# ProDoc_HyperCardReader_2024-07-06.net
KiCad netlist of a schematic drawn in EasyEDA Pro
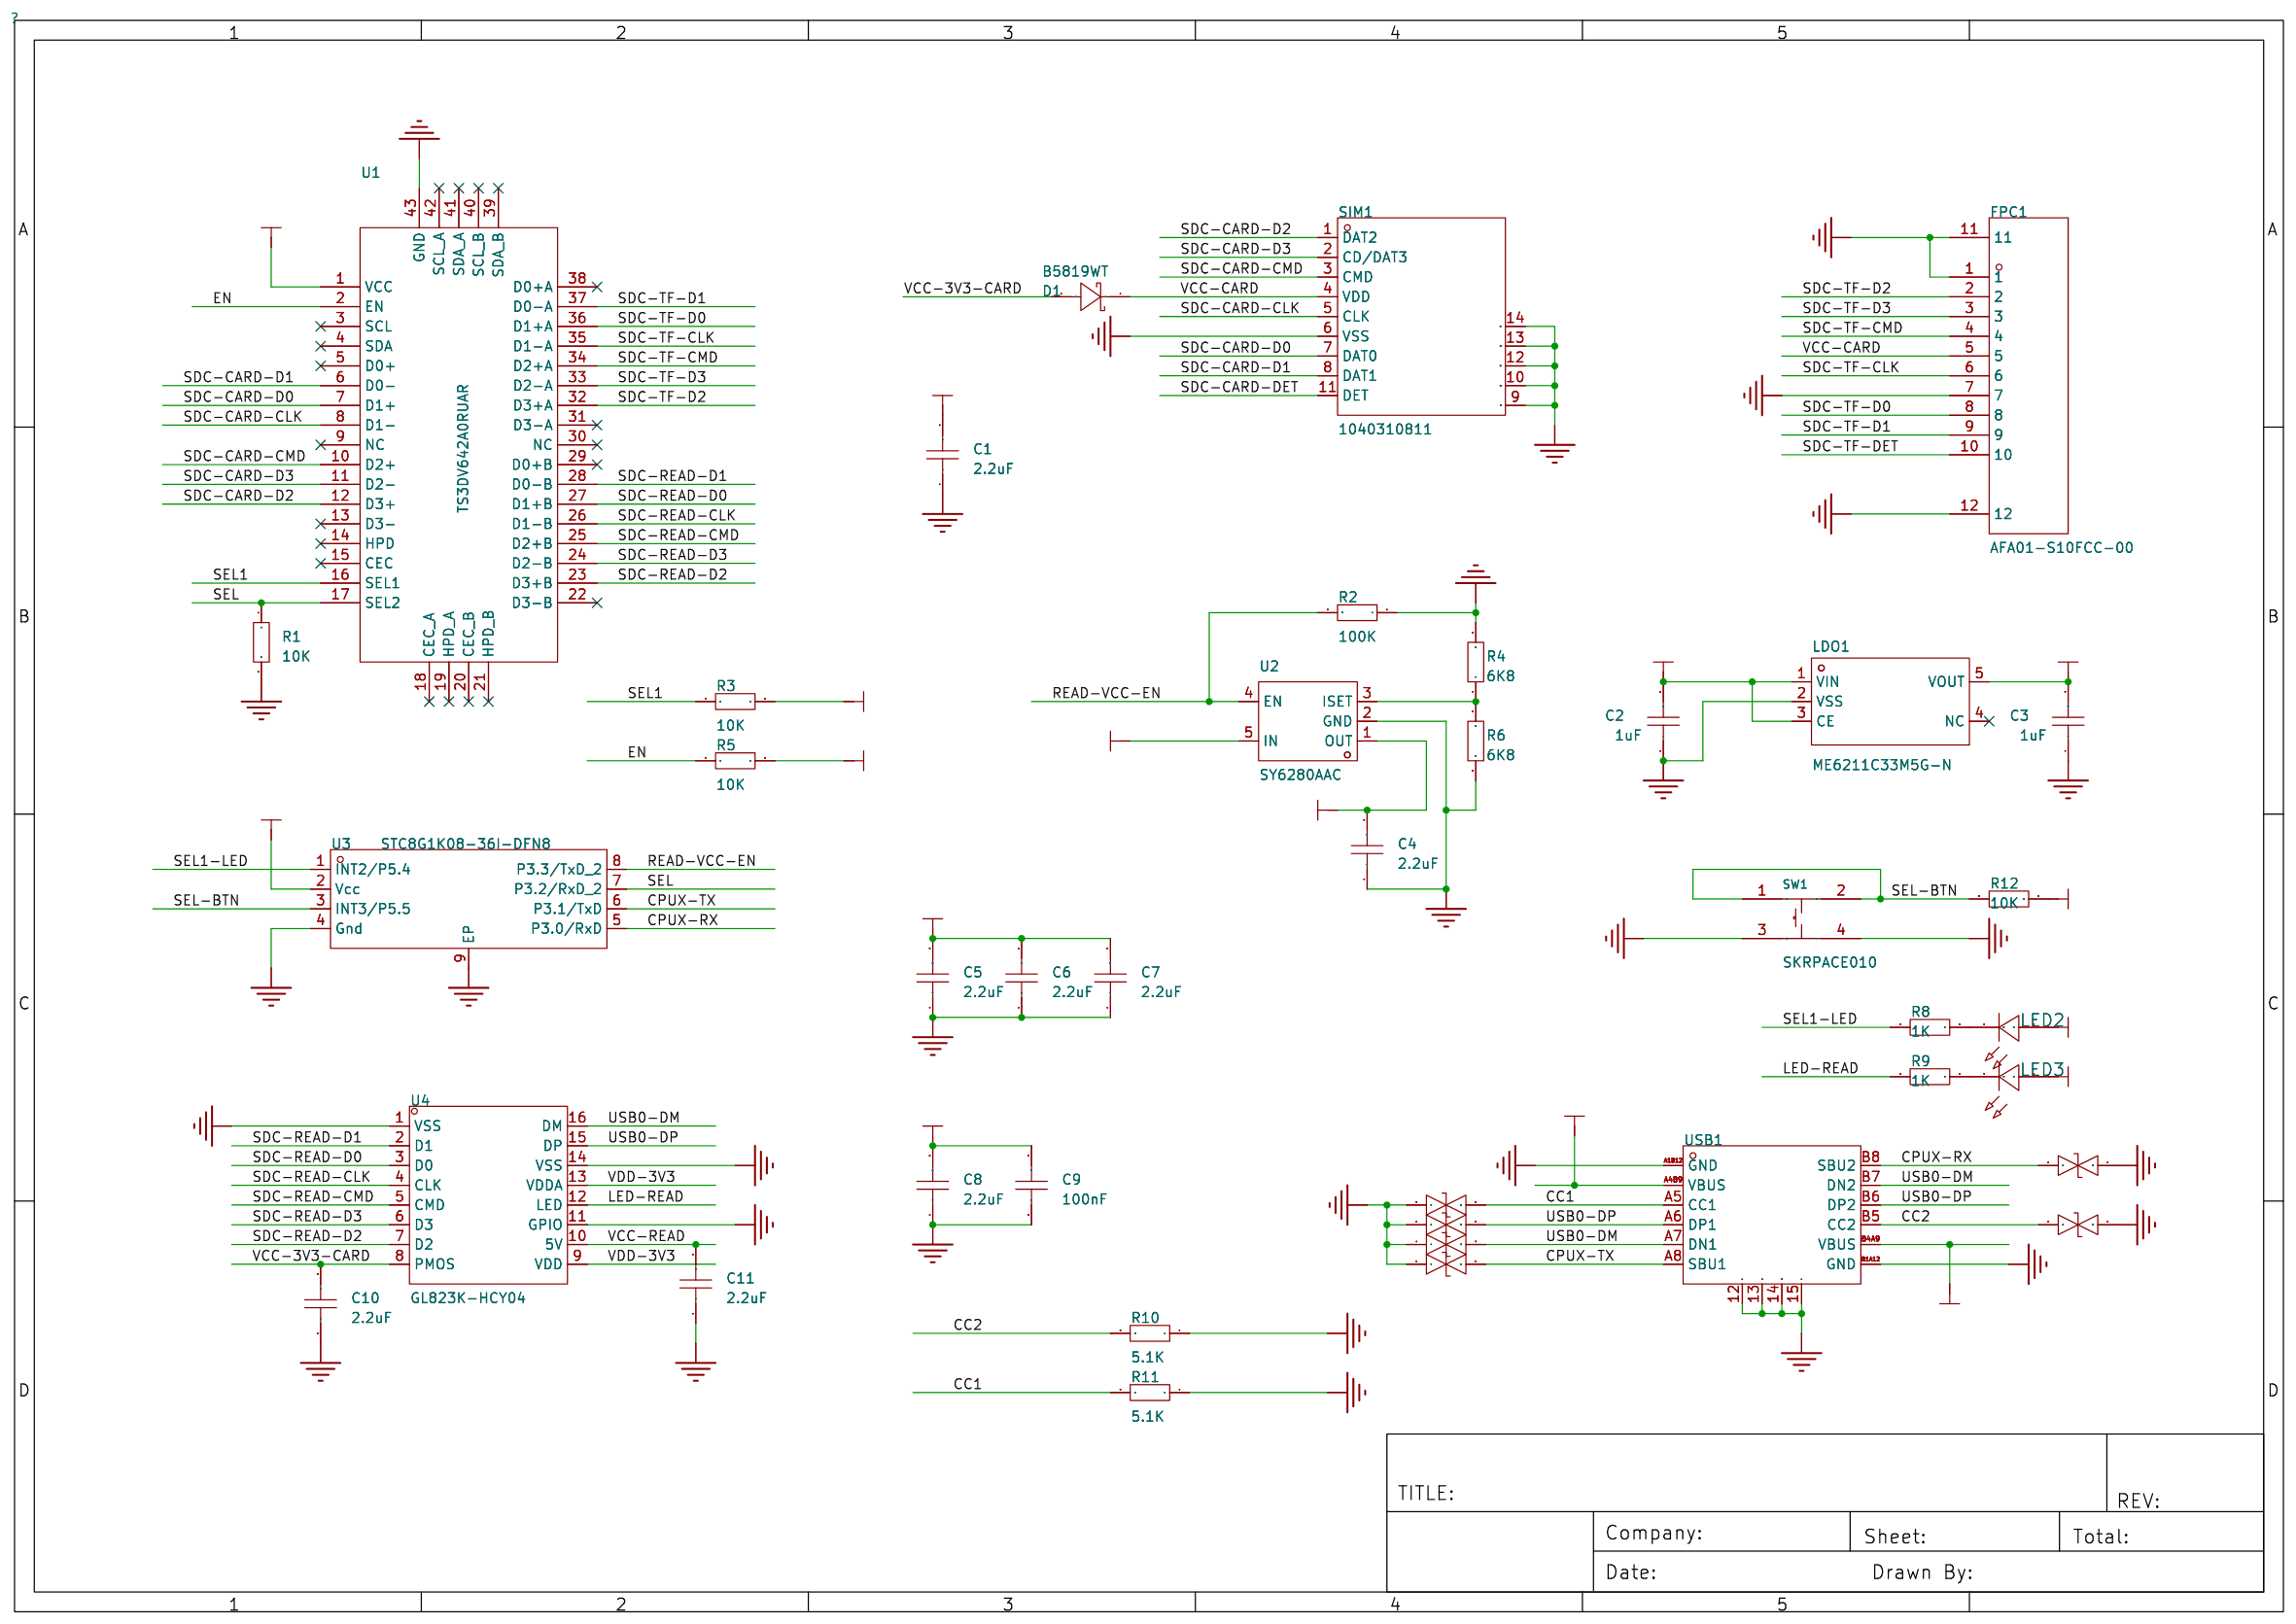
[diagram p0: schematic sheet]

(export (version "E")
  (design (tool "Eeschema 10.0.6"))
  (components
    (comp (ref "C1")
      (value "2.2uF")
      (footprint "easyedapro:C0402")
      (libsource (lib "easyedapro") (part "CapAcitance"))
    )
    (comp (ref "C2")
      (value "1uF")
      (footprint "easyedapro:C0402")
      (libsource (lib "easyedapro") (part "CapAcitance"))
    )
    (comp (ref "C3")
      (value "1uF")
      (footprint "easyedapro:C0402")
      (libsource (lib "easyedapro") (part "CapAcitance"))
    )
    (comp (ref "C4")
      (value "2.2uF")
      (footprint "easyedapro:C0402")
      (libsource (lib "easyedapro") (part "CapAcitance"))
    )
    (comp (ref "C5")
      (value "2.2uF")
      (footprint "easyedapro:C0402")
      (libsource (lib "easyedapro") (part "CapAcitance"))
    )
    (comp (ref "C6")
      (value "2.2uF")
      (footprint "easyedapro:C0402")
      (libsource (lib "easyedapro") (part "CapAcitance"))
    )
    (comp (ref "C7")
      (value "2.2uF")
      (footprint "easyedapro:C0402")
      (libsource (lib "easyedapro") (part "CapAcitance"))
    )
    (comp (ref "C8")
      (value "2.2uF")
      (footprint "easyedapro:C0402")
      (libsource (lib "easyedapro") (part "CapAcitance"))
    )
    (comp (ref "C9")
      (value "100nF")
      (footprint "easyedapro:C0402")
      (libsource (lib "easyedapro") (part "CapAcitance"))
    )
    (comp (ref "C10")
      (value "2.2uF")
      (footprint "easyedapro:C0402")
      (libsource (lib "easyedapro") (part "CapAcitance"))
    )
    (comp (ref "C11")
      (value "2.2uF")
      (footprint "easyedapro:C0402")
      (libsource (lib "easyedapro") (part "CapAcitance"))
    )
    (comp (ref "D1")
      (value "B5819WT")
      (footprint "easyedapro:SOD-523_L1.2-W0.8-LS1.6-RD")
      (description "二极管配置:-;正向压降(Vf):600mV@200mA;直流反向耐压(Vr):40V;平均整流电流(Io):1A;")
      (fields (field (name "Manufacturer") "BORN(伯恩半导体)"))
      (libsource (lib "easyedapro") (part "B5819WT_C2997265"))
    )
    (comp (ref "D2")
      (value "0402ESDA-05N")
      (footprint "easyedapro:D0402-BI")
      (description "极性:Bidirectional;反向关断电压（典型值）:5V;击穿电压（最小值）:-;箝位电压:50V;峰值脉冲电流（10/1000us）:-;")
      (fields (field (name "Manufacturer") "BORN伯恩半导体"))
      (libsource (lib "easyedapro") (part "0402ESDA-05N"))
    )
    (comp (ref "D3")
      (value "0402ESDA-05N")
      (footprint "easyedapro:D0402-BI")
      (description "极性:Bidirectional;反向关断电压（典型值）:5V;击穿电压（最小值）:-;箝位电压:50V;峰值脉冲电流（10/1000us）:-;")
      (fields (field (name "Manufacturer") "BORN伯恩半导体"))
      (libsource (lib "easyedapro") (part "0402ESDA-05N"))
    )
    (comp (ref "D4")
      (value "0402ESDA-05N")
      (footprint "easyedapro:D0402-BI")
      (description "极性:Bidirectional;反向关断电压（典型值）:5V;击穿电压（最小值）:-;箝位电压:50V;峰值脉冲电流（10/1000us）:-;")
      (fields (field (name "Manufacturer") "BORN伯恩半导体"))
      (libsource (lib "easyedapro") (part "0402ESDA-05N"))
    )
    (comp (ref "D5")
      (value "0402ESDA-05N")
      (footprint "easyedapro:D0402-BI")
      (description "极性:Bidirectional;反向关断电压（典型值）:5V;击穿电压（最小值）:-;箝位电压:50V;峰值脉冲电流（10/1000us）:-;")
      (fields (field (name "Manufacturer") "BORN伯恩半导体"))
      (libsource (lib "easyedapro") (part "0402ESDA-05N"))
    )
    (comp (ref "D6")
      (value "0402ESDA-05N")
      (footprint "easyedapro:D0402-BI")
      (description "极性:Bidirectional;反向关断电压（典型值）:5V;击穿电压（最小值）:-;箝位电压:50V;峰值脉冲电流（10/1000us）:-;")
      (fields (field (name "Manufacturer") "BORN伯恩半导体"))
      (libsource (lib "easyedapro") (part "0402ESDA-05N"))
    )
    (comp (ref "D7")
      (value "0402ESDA-05N")
      (footprint "easyedapro:D0402-BI")
      (description "极性:Bidirectional;反向关断电压（典型值）:5V;击穿电压（最小值）:-;箝位电压:50V;峰值脉冲电流（10/1000us）:-;")
      (fields (field (name "Manufacturer") "BORN伯恩半导体"))
      (libsource (lib "easyedapro") (part "0402ESDA-05N"))
    )
    (comp (ref "FPC1")
      (value "AFA01-S10FCC-00")
      (footprint "easyedapro:FPC-SMD_AFA01-S10FCC-00")
      (description "锁定特性:翻盖式;触点类型:下接;触点数量:10P;间距:1mm;安装类型:卧贴;")
      (fields (field (name "Manufacturer") "JS(钜硕电子)"))
      (libsource (lib "easyedapro") (part "AFA01-S10FCC-00"))
    )
    (comp (ref "LDO1")
      (value "ME6211C33M5G-N")
      (footprint "easyedapro:SOT-23-5_L3.0-W1.7-P0.95-LS2.8-BL")
      (description "输出类型:固定;最大输入电压:6V;输出电压:3.3V;最大输出电流:500mA;电源纹波抑制比(PSRR):70dB;输出极性:正极;")
      (fields (field (name "Manufacturer") "MICRONE(南京微盟)"))
      (libsource (lib "easyedapro") (part "ME6211C33M5G-N"))
    )
    (comp (ref "LED2")
      (value "~")
      (footprint "easyedapro:LED_0603")
      (libsource (lib "easyedapro") (part "LED_R"))
    )
    (comp (ref "LED3")
      (value "~")
      (footprint "easyedapro:LED_0603")
      (libsource (lib "easyedapro") (part "LED_R"))
    )
    (comp (ref "R1") (value "10K") (footprint "easyedapro:R0201") (libsource (lib "easyedapro") (part "电阻")))
    (comp (ref "R2") (value "100K") (footprint "easyedapro:R0201") (libsource (lib "easyedapro") (part "电阻")))
    (comp (ref "R3") (value "10K") (footprint "easyedapro:R0201") (libsource (lib "easyedapro") (part "电阻")))
    (comp (ref "R4") (value "6K8") (footprint "easyedapro:R0201") (libsource (lib "easyedapro") (part "电阻")))
    (comp (ref "R5") (value "10K") (footprint "easyedapro:R0201") (libsource (lib "easyedapro") (part "电阻")))
    (comp (ref "R6") (value "6K8") (footprint "easyedapro:R0201") (libsource (lib "easyedapro") (part "电阻")))
    (comp (ref "R8") (value "1K") (footprint "easyedapro:R0201") (libsource (lib "easyedapro") (part "电阻")))
    (comp (ref "R9") (value "1K") (footprint "easyedapro:R0201") (libsource (lib "easyedapro") (part "电阻")))
    (comp (ref "R10")
      (value "5.1K")
      (footprint "easyedapro:R0201")
      (libsource (lib "easyedapro") (part "电阻"))
    )
    (comp (ref "R11")
      (value "5.1K")
      (footprint "easyedapro:R0201")
      (libsource (lib "easyedapro") (part "电阻"))
    )
    (comp (ref "R12") (value "10K") (footprint "easyedapro:R0201") (libsource (lib "easyedapro") (part "电阻")))
    (comp (ref "SIM1")
      (value "1040310811")
      (footprint "easyedapro:SIM-SMD_8P-1040310811")
      (description "卡连接方式:拔插式;卡类型:MicroSD卡(TF卡);连接器类型:卡座;本体最大高度:1.42mm;触头镀层:金;工作温度范围:-;")
      (fields (field (name "Manufacturer") "MOLEX"))
      (libsource (lib "easyedapro") (part "1040310811"))
    )
    (comp (ref "SW1")
      (value "SKRPACE010")
      (footprint "easyedapro:KEY-SMD_4P-L4.2-W3.2-P2.20-LS4.6")
      (description "电路结构:单刀单掷;按钮形状:椭圆形按钮;安装方式:立贴;开关长度:4.2mm;开关宽度:3.2mm;开关高度:2.5mm;触点电流:50mA;额定电压(DC):16V;带灯:-;机械寿命:-;")
      (fields (field (name "Manufacturer") "ALPSALPINE(阿尔卑斯阿尔派)"))
      (libsource (lib "easyedapro") (part "SKRPACE010"))
    )
    (comp (ref "U1")
      (value "TS3DV642A0RUAR")
      (footprint "easyedapro:WFQFN-42_L9.0-W3.5-P0.50-BL-EP")
      (description "开关电路:-;")
      (fields (field (name "Manufacturer") "TI(德州仪器)"))
      (libsource (lib "easyedapro") (part "TS3DV642A0RUAR"))
    )
    (comp (ref "U2")
      (value "SY6280AAC")
      (footprint "easyedapro:SOT-23-5_L3.0-W1.7-P0.95-LS2.8-BL")
      (description "低能耗配电开关")
      (fields (field (name "Manufacturer") "silergy(矽力杰)"))
      (libsource (lib "easyedapro") (part "SY6280AAC"))
    )
    (comp (ref "U3")
      (value "STC8G1K08-36I-DFN8")
      (footprint "easyedapro:DFN-8_L3.0-W3.0-P0.50-BL-EP")
      (description "CPU内核:51系列;程序存储容量:8KB;RAM总容量:1.25KB;GPIO端口数量:6;工作电压范围:1.9V~5.5V;CPU最大主频:-;程序存储器类型:FLASH;")
      (fields (field (name "Manufacturer") "STC(宏晶)"))
      (libsource (lib "easyedapro") (part "STC8G1K08-36I-DFN8"))
    )
    (comp (ref "U4")
      (value "GL823K-HCY04")
      (footprint "easyedapro:SSOP-16_L4.9-W3.9-P0.64-LS6.0-BL")
      (description "应用功能:-;接口协议:-;")
      (fields (field (name "Manufacturer") "GENESYS(创惟)"))
      (libsource (lib "easyedapro") (part "GL823K-HCY04"))
    )
    (comp (ref "USB1")
      (value "~")
      (footprint "easyedapro:USB-C-SMD_TYPEC-304-BCP16-1")
      (fields (field (name "Manufacturer Part") "TYPEC-304-BCP16") (field (name "Manufacturer") "XUNPU"))
      (libsource (lib "easyedapro") (part "TYPEC-304-BCP16"))
    )
  )
  (nets
    (net (code "1") (name "/CC1") (class "Default")
      (node (ref "D3") (pin "2") (pinfunction "2_2") (pintype "unspecified"))
      (node (ref "R11") (pin "2") (pinfunction "2_2") (pintype "input"))
      (node (ref "USB1") (pin "A5") (pinfunction "CC1_A5") (pintype "unspecified"))
    )
    (net (code "2") (name "/CC2") (class "Default")
      (node (ref "D6") (pin "2") (pinfunction "2_2") (pintype "unspecified"))
      (node (ref "R10") (pin "2") (pinfunction "2_2") (pintype "input"))
      (node (ref "USB1") (pin "B5") (pinfunction "CC2_B5") (pintype "unspecified"))
    )
    (net (code "3") (name "/CPUX-RX") (class "Default")
      (node (ref "D2") (pin "2") (pinfunction "2_2") (pintype "unspecified"))
      (node (ref "U3") (pin "5") (pinfunction "P3.0/RxD_5") (pintype "input"))
      (node (ref "USB1") (pin "B8") (pinfunction "SBU2_B8") (pintype "unspecified"))
    )
    (net (code "4") (name "/CPUX-TX") (class "Default")
      (node (ref "D7") (pin "2") (pinfunction "2_2") (pintype "unspecified"))
      (node (ref "U3") (pin "6") (pinfunction "P3.1/TxD_6") (pintype "input"))
      (node (ref "USB1") (pin "A8") (pinfunction "SBU1_A8") (pintype "unspecified"))
    )
    (net (code "5") (name "/EN") (class "Default")
      (node (ref "R5") (pin "1") (pinfunction "1_1") (pintype "input"))
      (node (ref "U1") (pin "2") (pinfunction "EN_2") (pintype "input"))
    )
    (net (code "6") (name "/LED-READ") (class "Default")
      (node (ref "R9") (pin "2") (pinfunction "2_2") (pintype "input"))
      (node (ref "U4") (pin "12") (pinfunction "LED_12") (pintype "unspecified"))
    )
    (net (code "7") (name "/READ-VCC-EN") (class "Default")
      (node (ref "R2") (pin "2") (pinfunction "2_2") (pintype "input"))
      (node (ref "U2") (pin "4") (pinfunction "EN_4") (pintype "unspecified"))
      (node (ref "U3") (pin "8") (pinfunction "P3.3/TxD_2_8") (pintype "input"))
    )
    (net (code "8") (name "/SDC-CARD-CLK") (class "Default")
      (node (ref "SIM1") (pin "5") (pinfunction "CLK_5") (pintype "input"))
      (node (ref "U1") (pin "8") (pinfunction "D1-_8") (pintype "input"))
    )
    (net (code "9") (name "/SDC-CARD-CMD") (class "Default")
      (node (ref "SIM1") (pin "3") (pinfunction "CMD_3") (pintype "input"))
      (node (ref "U1") (pin "10") (pinfunction "D2+_10") (pintype "input"))
    )
    (net (code "10") (name "/SDC-CARD-D0") (class "Default")
      (node (ref "SIM1") (pin "7") (pinfunction "DAT0_7") (pintype "input"))
      (node (ref "U1") (pin "7") (pinfunction "D1+_7") (pintype "input"))
    )
    (net (code "11") (name "/SDC-CARD-D1") (class "Default")
      (node (ref "SIM1") (pin "8") (pinfunction "DAT1_8") (pintype "input"))
      (node (ref "U1") (pin "6") (pinfunction "D0-_6") (pintype "input"))
    )
    (net (code "12") (name "/SDC-CARD-D2") (class "Default")
      (node (ref "SIM1") (pin "1") (pinfunction "DAT2_1") (pintype "input"))
      (node (ref "U1") (pin "12") (pinfunction "D3+_12") (pintype "input"))
    )
    (net (code "13") (name "/SDC-CARD-D3") (class "Default")
      (node (ref "SIM1") (pin "2") (pinfunction "CD/DAT3_2") (pintype "input"))
      (node (ref "U1") (pin "11") (pinfunction "D2-_11") (pintype "input"))
    )
    (net (code "14") (name "/SDC-CARD-DET") (class "Default")
      (node (ref "SIM1") (pin "11") (pinfunction "DET_11") (pintype "input"))
    )
    (net (code "15") (name "/SDC-READ-CLK") (class "Default")
      (node (ref "U1") (pin "26") (pinfunction "D1-B_26") (pintype "input"))
      (node (ref "U4") (pin "4") (pinfunction "CLK_4") (pintype "unspecified"))
    )
    (net (code "16") (name "/SDC-READ-CMD") (class "Default")
      (node (ref "U1") (pin "25") (pinfunction "D2+B_25") (pintype "input"))
      (node (ref "U4") (pin "5") (pinfunction "CMD_5") (pintype "unspecified"))
    )
    (net (code "17") (name "/SDC-READ-D0") (class "Default")
      (node (ref "U1") (pin "27") (pinfunction "D1+B_27") (pintype "input"))
      (node (ref "U4") (pin "3") (pinfunction "D0_3") (pintype "unspecified"))
    )
    (net (code "18") (name "/SDC-READ-D1") (class "Default")
      (node (ref "U1") (pin "28") (pinfunction "D0-B_28") (pintype "input"))
      (node (ref "U4") (pin "2") (pinfunction "D1_2") (pintype "unspecified"))
    )
    (net (code "19") (name "/SDC-READ-D2") (class "Default")
      (node (ref "U1") (pin "23") (pinfunction "D3+B_23") (pintype "input"))
      (node (ref "U4") (pin "7") (pinfunction "D2_7") (pintype "unspecified"))
    )
    (net (code "20") (name "/SDC-READ-D3") (class "Default")
      (node (ref "U1") (pin "24") (pinfunction "D2-B_24") (pintype "input"))
      (node (ref "U4") (pin "6") (pinfunction "D3_6") (pintype "unspecified"))
    )
    (net (code "21") (name "/SDC-TF-CLK") (class "Default")
      (node (ref "FPC1") (pin "6") (pinfunction "6_6") (pintype "unspecified"))
      (node (ref "U1") (pin "35") (pinfunction "D1-A_35") (pintype "input"))
    )
    (net (code "22") (name "/SDC-TF-CMD") (class "Default")
      (node (ref "FPC1") (pin "4") (pinfunction "4_4") (pintype "unspecified"))
      (node (ref "U1") (pin "34") (pinfunction "D2+A_34") (pintype "input"))
    )
    (net (code "23") (name "/SDC-TF-D0") (class "Default")
      (node (ref "FPC1") (pin "8") (pinfunction "8_8") (pintype "unspecified"))
      (node (ref "U1") (pin "36") (pinfunction "D1+A_36") (pintype "input"))
    )
    (net (code "24") (name "/SDC-TF-D1") (class "Default")
      (node (ref "FPC1") (pin "9") (pinfunction "9_9") (pintype "unspecified"))
      (node (ref "U1") (pin "37") (pinfunction "D0-A_37") (pintype "input"))
    )
    (net (code "25") (name "/SDC-TF-D2") (class "Default")
      (node (ref "FPC1") (pin "2") (pinfunction "2_2") (pintype "unspecified"))
      (node (ref "U1") (pin "32") (pinfunction "D3+A_32") (pintype "input"))
    )
    (net (code "26") (name "/SDC-TF-D3") (class "Default")
      (node (ref "FPC1") (pin "3") (pinfunction "3_3") (pintype "unspecified"))
      (node (ref "U1") (pin "33") (pinfunction "D2-A_33") (pintype "input"))
    )
    (net (code "27") (name "/SDC-TF-DET") (class "Default")
      (node (ref "FPC1") (pin "10") (pinfunction "10_10") (pintype "unspecified"))
    )
    (net (code "28") (name "/SEL") (class "Default")
      (node (ref "R1") (pin "1") (pinfunction "1_1") (pintype "input"))
      (node (ref "U1") (pin "17") (pinfunction "SEL2_17") (pintype "input"))
      (node (ref "U3") (pin "7") (pinfunction "P3.2/RxD_2_7") (pintype "input"))
    )
    (net (code "29") (name "/SEL-BTN") (class "Default")
      (node (ref "R12") (pin "2") (pinfunction "2_2") (pintype "input"))
      (node (ref "SW1") (pin "1") (pinfunction "1_1") (pintype "input"))
      (node (ref "SW1") (pin "2") (pinfunction "2_2") (pintype "input"))
      (node (ref "U3") (pin "3") (pinfunction "INT3/P5.5_3") (pintype "input"))
    )
    (net (code "30") (name "/SEL1") (class "Default")
      (node (ref "R3") (pin "1") (pinfunction "1_1") (pintype "input"))
      (node (ref "U1") (pin "16") (pinfunction "SEL1_16") (pintype "input"))
    )
    (net (code "31") (name "/SEL1-LED") (class "Default")
      (node (ref "R8") (pin "2") (pinfunction "2_2") (pintype "input"))
      (node (ref "U3") (pin "1") (pinfunction "INT2/P5.4_1") (pintype "input"))
    )
    (net (code "32") (name "/USB0-DM") (class "Default")
      (node (ref "D5") (pin "2") (pinfunction "2_2") (pintype "unspecified"))
      (node (ref "U4") (pin "16") (pinfunction "DM_16") (pintype "unspecified"))
      (node (ref "USB1") (pin "A7") (pinfunction "DN1_A7") (pintype "unspecified"))
      (node (ref "USB1") (pin "B7") (pinfunction "DN2_B7") (pintype "unspecified"))
    )
    (net (code "33") (name "/USB0-DP") (class "Default")
      (node (ref "D4") (pin "2") (pinfunction "2_2") (pintype "unspecified"))
      (node (ref "U4") (pin "15") (pinfunction "DP_15") (pintype "unspecified"))
      (node (ref "USB1") (pin "A6") (pinfunction "DP1_A6") (pintype "unspecified"))
      (node (ref "USB1") (pin "B6") (pinfunction "DP2_B6") (pintype "unspecified"))
    )
    (net (code "34") (name "/VCC-3V3-CARD") (class "Default")
      (node (ref "C10") (pin "2") (pinfunction "2_2") (pintype "input"))
      (node (ref "D1") (pin "2") (pinfunction "A_2") (pintype "unspecified"))
      (node (ref "U4") (pin "8") (pinfunction "PMOS_8") (pintype "unspecified"))
    )
    (net (code "35") (name "GND") (class "Default")
      (node (ref "C1") (pin "1") (pinfunction "1_1") (pintype "input"))
      (node (ref "C10") (pin "1") (pinfunction "1_1") (pintype "input"))
      (node (ref "C11") (pin "1") (pinfunction "1_1") (pintype "input"))
      (node (ref "C2") (pin "1") (pinfunction "1_1") (pintype "input"))
      (node (ref "C3") (pin "1") (pinfunction "1_1") (pintype "input"))
      (node (ref "C4") (pin "1") (pinfunction "1_1") (pintype "input"))
      (node (ref "C5") (pin "1") (pinfunction "1_1") (pintype "input"))
      (node (ref "C6") (pin "1") (pinfunction "1_1") (pintype "input"))
      (node (ref "C7") (pin "1") (pinfunction "1_1") (pintype "input"))
      (node (ref "C8") (pin "1") (pinfunction "1_1") (pintype "input"))
      (node (ref "C9") (pin "1") (pinfunction "1_1") (pintype "input"))
      (node (ref "D2") (pin "1") (pinfunction "1_1") (pintype "unspecified"))
      (node (ref "D3") (pin "1") (pinfunction "1_1") (pintype "unspecified"))
      (node (ref "D4") (pin "1") (pinfunction "1_1") (pintype "unspecified"))
      (node (ref "D5") (pin "1") (pinfunction "1_1") (pintype "unspecified"))
      (node (ref "D6") (pin "1") (pinfunction "1_1") (pintype "unspecified"))
      (node (ref "D7") (pin "1") (pinfunction "1_1") (pintype "unspecified"))
      (node (ref "FPC1") (pin "1") (pinfunction "1_1") (pintype "unspecified"))
      (node (ref "FPC1") (pin "11") (pinfunction "11_11") (pintype "unspecified"))
      (node (ref "FPC1") (pin "12") (pinfunction "12_12") (pintype "unspecified"))
      (node (ref "FPC1") (pin "7") (pinfunction "7_7") (pintype "unspecified"))
      (node (ref "LDO1") (pin "2") (pinfunction "VSS_2") (pintype "input"))
      (node (ref "R1") (pin "2") (pinfunction "2_2") (pintype "input"))
      (node (ref "R10") (pin "1") (pinfunction "1_1") (pintype "input"))
      (node (ref "R11") (pin "1") (pinfunction "1_1") (pintype "input"))
      (node (ref "R2") (pin "1") (pinfunction "1_1") (pintype "input"))
      (node (ref "R4") (pin "2") (pinfunction "2_2") (pintype "input"))
      (node (ref "R6") (pin "1") (pinfunction "1_1") (pintype "input"))
      (node (ref "SIM1") (pin "10") (pinfunction "10_10") (pintype "input"))
      (node (ref "SIM1") (pin "12") (pinfunction "12_12") (pintype "input"))
      (node (ref "SIM1") (pin "13") (pinfunction "13_13") (pintype "input"))
      (node (ref "SIM1") (pin "14") (pinfunction "14_14") (pintype "input"))
      (node (ref "SIM1") (pin "6") (pinfunction "VSS_6") (pintype "input"))
      (node (ref "SIM1") (pin "9") (pinfunction "9_9") (pintype "input"))
      (node (ref "SW1") (pin "3") (pinfunction "3_3") (pintype "input"))
      (node (ref "SW1") (pin "4") (pinfunction "4_4") (pintype "input"))
      (node (ref "U1") (pin "43") (pinfunction "GND_43") (pintype "input"))
      (node (ref "U2") (pin "2") (pinfunction "GND_2") (pintype "unspecified"))
      (node (ref "U3") (pin "4") (pinfunction "Gnd_4") (pintype "input"))
      (node (ref "U3") (pin "9") (pinfunction "EP_9") (pintype "input"))
      (node (ref "U4") (pin "1") (pinfunction "VSS_1") (pintype "unspecified"))
      (node (ref "U4") (pin "11") (pinfunction "GPIO_11") (pintype "unspecified"))
      (node (ref "U4") (pin "14") (pinfunction "VSS_14") (pintype "unspecified"))
      (node (ref "USB1") (pin "12") (pinfunction "1_12") (pintype "unspecified"))
      (node (ref "USB1") (pin "13") (pinfunction "2_13") (pintype "unspecified"))
      (node (ref "USB1") (pin "14") (pinfunction "3_14") (pintype "unspecified"))
      (node (ref "USB1") (pin "15") (pinfunction "4_15") (pintype "unspecified"))
      (node (ref "USB1") (pin "A1B12") (pinfunction "GND_A1B12") (pintype "unspecified"))
      (node (ref "USB1") (pin "B1A12") (pinfunction "GND_B1A12") (pintype "unspecified"))
    )
    (net (code "36") (name "Net-(LED2-C)") (class "Default")
      (node (ref "LED2") (pin "1") (pinfunction "C_1") (pintype "input"))
      (node (ref "R8") (pin "1") (pinfunction "1_1") (pintype "input"))
    )
    (net (code "37") (name "Net-(LED3-C)") (class "Default")
      (node (ref "LED3") (pin "1") (pinfunction "C_1") (pintype "input"))
      (node (ref "R9") (pin "1") (pinfunction "1_1") (pintype "input"))
    )
    (net (code "38") (name "Net-(U2-ISET)") (class "Default")
      (node (ref "R4") (pin "1") (pinfunction "1_1") (pintype "input"))
      (node (ref "R6") (pin "2") (pinfunction "2_2") (pintype "input"))
      (node (ref "U2") (pin "3") (pinfunction "ISET_3") (pintype "unspecified"))
    )
    (net (code "39") (name "VBUS-USB") (class "Default")
      (node (ref "C2") (pin "2") (pinfunction "2_2") (pintype "input"))
      (node (ref "C5") (pin "2") (pinfunction "2_2") (pintype "input"))
      (node (ref "C6") (pin "2") (pinfunction "2_2") (pintype "input"))
      (node (ref "C7") (pin "2") (pinfunction "2_2") (pintype "input"))
      (node (ref "LDO1") (pin "1") (pinfunction "VIN_1") (pintype "input"))
      (node (ref "LDO1") (pin "3") (pinfunction "CE_3") (pintype "input"))
      (node (ref "U2") (pin "5") (pinfunction "IN_5") (pintype "unspecified"))
      (node (ref "USB1") (pin "A4B9") (pinfunction "VBUS_A4B9") (pintype "unspecified"))
      (node (ref "USB1") (pin "B4A9") (pinfunction "VBUS_B4A9") (pintype "unspecified"))
    )
    (net (code "40") (name "VCC-3V3-LDO") (class "Default")
      (node (ref "C3") (pin "2") (pinfunction "2_2") (pintype "input"))
      (node (ref "LDO1") (pin "5") (pinfunction "VOUT_5") (pintype "input"))
      (node (ref "LED2") (pin "2") (pinfunction "A_2") (pintype "input"))
      (node (ref "R12") (pin "1") (pinfunction "1_1") (pintype "input"))
      (node (ref "R3") (pin "2") (pinfunction "2_2") (pintype "input"))
      (node (ref "R5") (pin "2") (pinfunction "2_2") (pintype "input"))
      (node (ref "U1") (pin "1") (pinfunction "VCC_1") (pintype "input"))
      (node (ref "U3") (pin "2") (pinfunction "Vcc_2") (pintype "input"))
    )
    (net (code "41") (name "VCC-CARD") (class "Default")
      (node (ref "C1") (pin "2") (pinfunction "2_2") (pintype "input"))
      (node (ref "D1") (pin "1") (pinfunction "K_1") (pintype "unspecified"))
      (node (ref "FPC1") (pin "5") (pinfunction "5_5") (pintype "unspecified"))
      (node (ref "SIM1") (pin "4") (pinfunction "VDD_4") (pintype "input"))
    )
    (net (code "42") (name "VCC-READ") (class "Default")
      (node (ref "C11") (pin "2") (pinfunction "2_2") (pintype "input"))
      (node (ref "C4") (pin "2") (pinfunction "2_2") (pintype "input"))
      (node (ref "U2") (pin "1") (pinfunction "OUT_1") (pintype "unspecified"))
      (node (ref "U4") (pin "10") (pinfunction "5V_10") (pintype "unspecified"))
    )
    (net (code "43") (name "VDD-3V3") (class "Default")
      (node (ref "C8") (pin "2") (pinfunction "2_2") (pintype "input"))
      (node (ref "C9") (pin "2") (pinfunction "2_2") (pintype "input"))
      (node (ref "LED3") (pin "2") (pinfunction "A_2") (pintype "input"))
      (node (ref "U4") (pin "13") (pinfunction "VDDA_13") (pintype "unspecified"))
      (node (ref "U4") (pin "9") (pinfunction "VDD_9") (pintype "unspecified"))
    )
    (net (code "44") (name "unconnected-(LDO1-NC-Pad4)") (class "Default")
      (node (ref "LDO1") (pin "4") (pinfunction "NC_4") (pintype "input+no_connect"))
    )
    (net (code "45") (name "unconnected-(U1-CEC-Pad15)") (class "Default")
      (node (ref "U1") (pin "15") (pinfunction "CEC_15") (pintype "input+no_connect"))
    )
    (net (code "46") (name "unconnected-(U1-CEC_A-Pad18)") (class "Default")
      (node (ref "U1") (pin "18") (pinfunction "CEC_A_18") (pintype "input+no_connect"))
    )
    (net (code "47") (name "unconnected-(U1-CEC_B-Pad20)") (class "Default")
      (node (ref "U1") (pin "20") (pinfunction "CEC_B_20") (pintype "input+no_connect"))
    )
    (net (code "48") (name "unconnected-(U1-D0+-Pad5)") (class "Default")
      (node (ref "U1") (pin "5") (pinfunction "D0+_5") (pintype "input+no_connect"))
    )
    (net (code "49") (name "unconnected-(U1-D0+A-Pad38)") (class "Default")
      (node (ref "U1") (pin "38") (pinfunction "D0+A_38") (pintype "input+no_connect"))
    )
    (net (code "50") (name "unconnected-(U1-D0+B-Pad29)") (class "Default")
      (node (ref "U1") (pin "29") (pinfunction "D0+B_29") (pintype "input+no_connect"))
    )
    (net (code "51") (name "unconnected-(U1-D3--Pad13)") (class "Default")
      (node (ref "U1") (pin "13") (pinfunction "D3-_13") (pintype "input+no_connect"))
    )
    (net (code "52") (name "unconnected-(U1-D3-A-Pad31)") (class "Default")
      (node (ref "U1") (pin "31") (pinfunction "D3-A_31") (pintype "input+no_connect"))
    )
    (net (code "53") (name "unconnected-(U1-D3-B-Pad22)") (class "Default")
      (node (ref "U1") (pin "22") (pinfunction "D3-B_22") (pintype "input+no_connect"))
    )
    (net (code "54") (name "unconnected-(U1-HPD-Pad14)") (class "Default")
      (node (ref "U1") (pin "14") (pinfunction "HPD_14") (pintype "input+no_connect"))
    )
    (net (code "55") (name "unconnected-(U1-HPD_A-Pad19)") (class "Default")
      (node (ref "U1") (pin "19") (pinfunction "HPD_A_19") (pintype "input+no_connect"))
    )
    (net (code "56") (name "unconnected-(U1-HPD_B-Pad21)") (class "Default")
      (node (ref "U1") (pin "21") (pinfunction "HPD_B_21") (pintype "input+no_connect"))
    )
    (net (code "57") (name "unconnected-(U1-NC-Pad9)") (class "Default")
      (node (ref "U1") (pin "9") (pinfunction "NC_9") (pintype "input+no_connect"))
    )
    (net (code "58") (name "unconnected-(U1-NC-Pad30)") (class "Default")
      (node (ref "U1") (pin "30") (pinfunction "NC_30") (pintype "input+no_connect"))
    )
    (net (code "59") (name "unconnected-(U1-SCL-Pad3)") (class "Default")
      (node (ref "U1") (pin "3") (pinfunction "SCL_3") (pintype "input+no_connect"))
    )
    (net (code "60") (name "unconnected-(U1-SCL_A-Pad42)") (class "Default")
      (node (ref "U1") (pin "42") (pinfunction "SCL_A_42") (pintype "input+no_connect"))
    )
    (net (code "61") (name "unconnected-(U1-SCL_B-Pad40)") (class "Default")
      (node (ref "U1") (pin "40") (pinfunction "SCL_B_40") (pintype "input+no_connect"))
    )
    (net (code "62") (name "unconnected-(U1-SDA-Pad4)") (class "Default")
      (node (ref "U1") (pin "4") (pinfunction "SDA_4") (pintype "input+no_connect"))
    )
    (net (code "63") (name "unconnected-(U1-SDA_A-Pad41)") (class "Default")
      (node (ref "U1") (pin "41") (pinfunction "SDA_A_41") (pintype "input+no_connect"))
    )
    (net (code "64") (name "unconnected-(U1-SDA_B-Pad39)") (class "Default")
      (node (ref "U1") (pin "39") (pinfunction "SDA_B_39") (pintype "input+no_connect"))
    )
  )
)
